# 2LD-17-mk-1_4_0.net
KiCad netlist of a schematic drawn in EAGLE
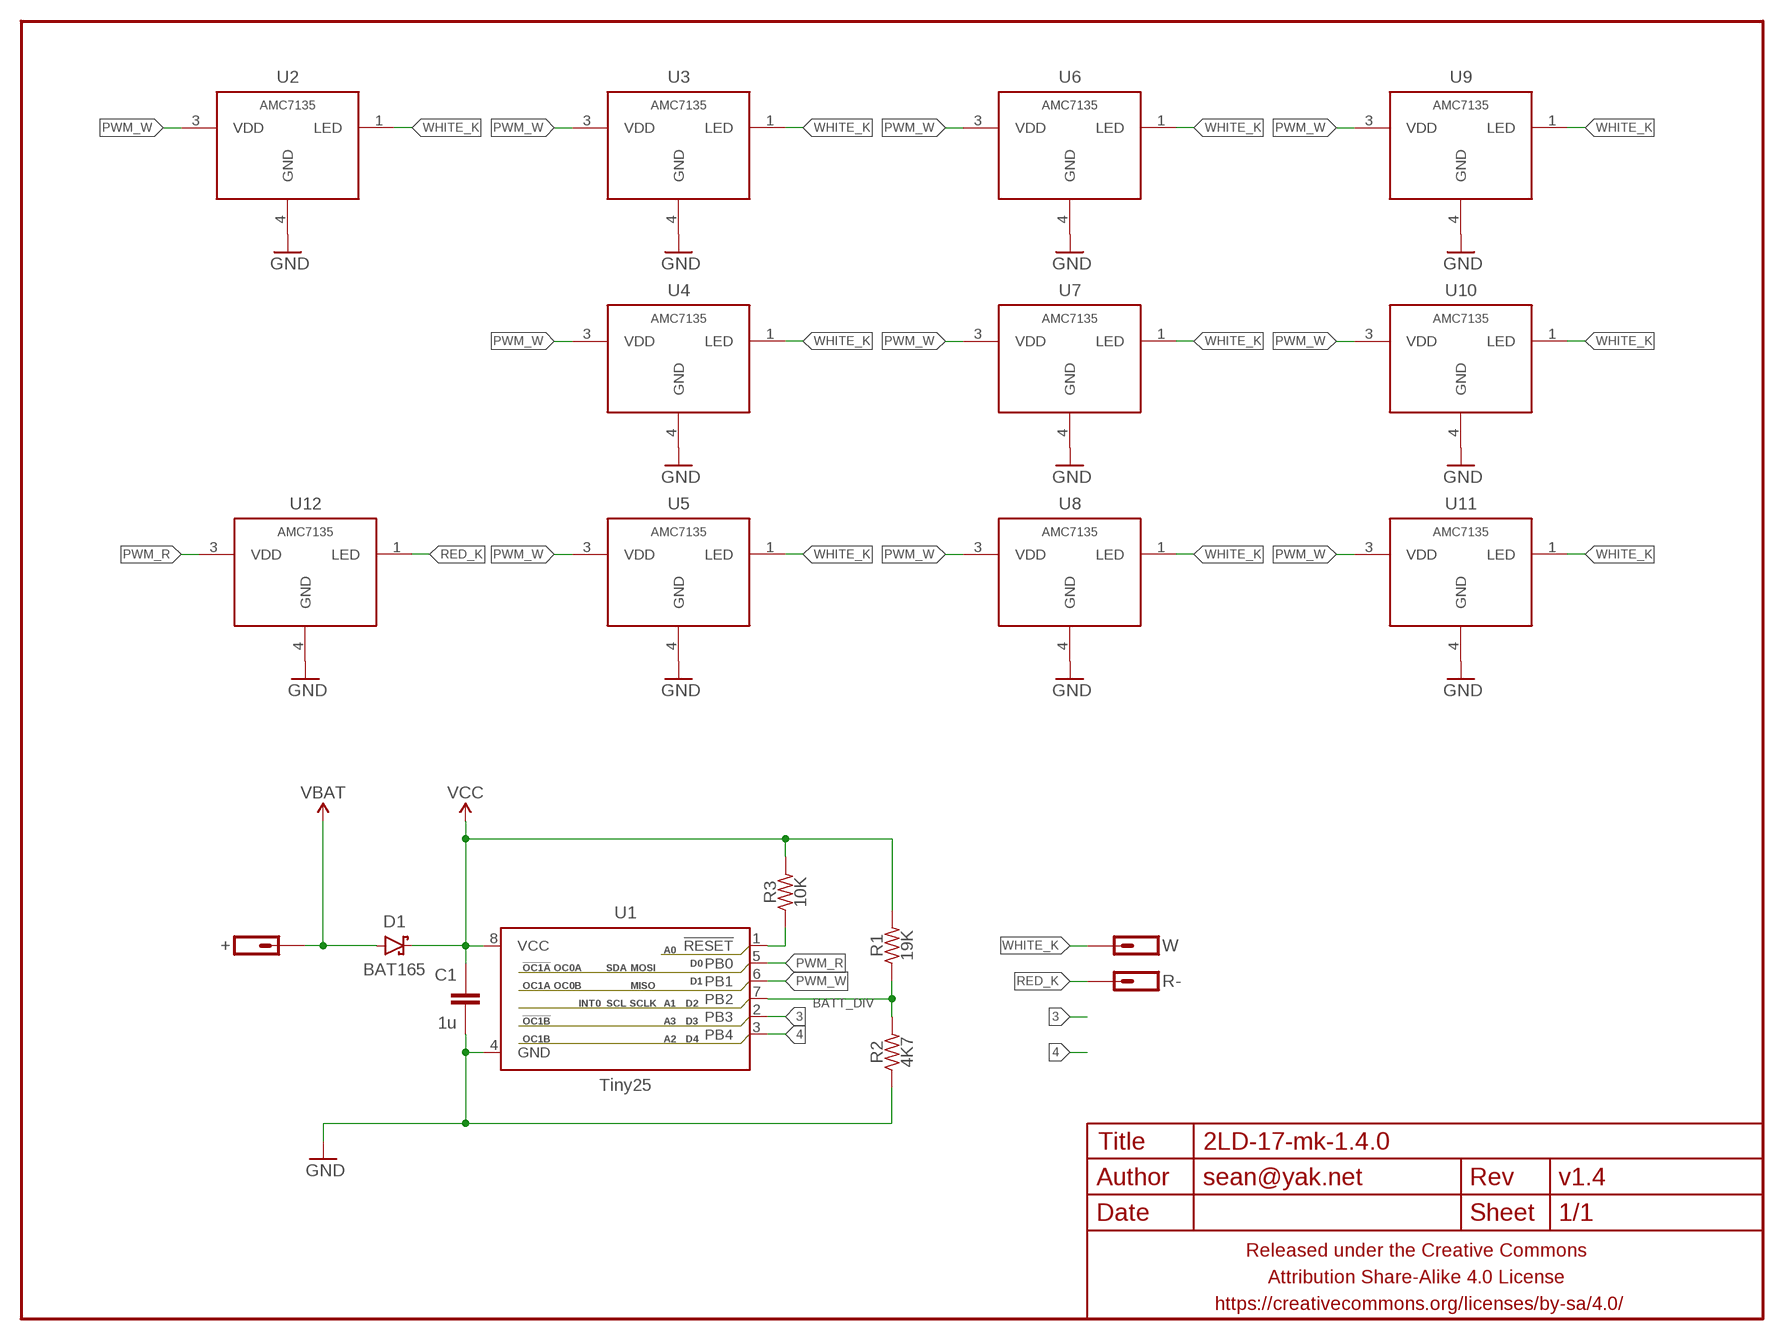
[diagram p0: schematic, sheet 1]

(export (version "E")
  (design (tool "Eeschema 10.0.6"))
  (components
    (comp (ref "+")
      (value "M011X01-0.9MM-CIR")
      (footprint "eagle-import:1X01-0.9MM-CIR")
      (libsource (lib "eagle-import") (part "M011X01-0.9MM-CIR"))
    )
    (comp (ref "C1")
      (value "1u")
      (footprint "eagle-import:C0402")
      (libsource (lib "eagle-import") (part "CAPACITOR-CERAMICC0402"))
    )
    (comp (ref "D1")
      (value "BAT165")
      (footprint "eagle-import:SOD323-SCHOTTKY")
      (libsource (lib "eagle-import") (part "DIODE-SCHOTTKYSOD323"))
    )
    (comp (ref "FRAME1")
      (value "FRAME-LETTERNO_PACKAGE")
      (footprint "eagle-import:DUMMY")
      (fields (field (name "DESIGNER") "sean@yak.net") (field (name "VERSION") "v1.4"))
      (libsource (lib "eagle-import") (part "FRAME-LETTERNO_PACKAGE"))
    )
    (comp (ref "R-")
      (value "M01SMD-1MM-DIA-NS")
      (footprint "eagle-import:1X01-SMD-1MM-DIA-NS")
      (libsource (lib "eagle-import") (part "M01SMD-1MM-DIA-NS"))
    )
    (comp (ref "R1")
      (value "19K")
      (footprint "eagle-import:R0402")
      (libsource (lib "eagle-import") (part "RESISTORR0402"))
    )
    (comp (ref "R2")
      (value "4K7")
      (footprint "eagle-import:R0402")
      (libsource (lib "eagle-import") (part "RESISTORR0402"))
    )
    (comp (ref "R3")
      (value "10K")
      (footprint "eagle-import:R0402")
      (libsource (lib "eagle-import") (part "RESISTORR0402"))
    )
    (comp (ref "U1")
      (value "Tiny25")
      (footprint "eagle-import:SO08-NARROWER")
      (libsource (lib "eagle-import") (part "ATTINY13SOIC-NARROWPADS"))
    )
    (comp (ref "U2")
      (value "AMC7135")
      (footprint "eagle-import:SOT89-NOTHERM-ROUNDED-LESS")
      (libsource (lib "eagle-import") (part "AMC7135SOT-89-NOTHERM-ROUNDED-LESS"))
    )
    (comp (ref "U3")
      (value "AMC7135")
      (footprint "eagle-import:SOT89-NOTHERM-ROUNDED-LESS")
      (libsource (lib "eagle-import") (part "AMC7135SOT-89-NOTHERM-ROUNDED-LESS"))
    )
    (comp (ref "U4")
      (value "AMC7135")
      (footprint "eagle-import:SOT89-NOTHERM-ROUNDED-LESS")
      (libsource (lib "eagle-import") (part "AMC7135SOT-89-NOTHERM-ROUNDED-LESS"))
    )
    (comp (ref "U5")
      (value "AMC7135")
      (footprint "eagle-import:SOT89-NOTHERM-ROUNDED-LESS")
      (libsource (lib "eagle-import") (part "AMC7135SOT-89-NOTHERM-ROUNDED-LESS"))
    )
    (comp (ref "U6")
      (value "AMC7135")
      (footprint "eagle-import:SOT89-NOTHERM-ROUNDED-LESS")
      (libsource (lib "eagle-import") (part "AMC7135SOT-89-NOTHERM-ROUNDED-LESS"))
    )
    (comp (ref "U7")
      (value "AMC7135")
      (footprint "eagle-import:SOT89-NOTHERM-ROUNDED-LESS")
      (libsource (lib "eagle-import") (part "AMC7135SOT-89-NOTHERM-ROUNDED-LESS"))
    )
    (comp (ref "U8")
      (value "AMC7135")
      (footprint "eagle-import:SOT89-NOTHERM-ROUNDED-LESS")
      (libsource (lib "eagle-import") (part "AMC7135SOT-89-NOTHERM-ROUNDED-LESS"))
    )
    (comp (ref "U9")
      (value "AMC7135")
      (footprint "eagle-import:SOT89-NOTHERM-ROUNDED-LESS")
      (libsource (lib "eagle-import") (part "AMC7135SOT-89-NOTHERM-ROUNDED-LESS"))
    )
    (comp (ref "U10")
      (value "AMC7135")
      (footprint "eagle-import:SOT89-NOTHERM-ROUNDED-LESS")
      (libsource (lib "eagle-import") (part "AMC7135SOT-89-NOTHERM-ROUNDED-LESS"))
    )
    (comp (ref "U11")
      (value "AMC7135")
      (footprint "eagle-import:SOT89-NOTHERM-ROUNDED-LESS")
      (libsource (lib "eagle-import") (part "AMC7135SOT-89-NOTHERM-ROUNDED-LESS"))
    )
    (comp (ref "U12")
      (value "AMC7135")
      (footprint "eagle-import:SOT89-NOTHERM-ROUNDED-LESS")
      (libsource (lib "eagle-import") (part "AMC7135SOT-89-NOTHERM-ROUNDED-LESS"))
    )
    (comp (ref "W")
      (value "M011X01-0.9MM-CIR")
      (footprint "eagle-import:1X01-0.9MM-CIR")
      (libsource (lib "eagle-import") (part "M011X01-0.9MM-CIR"))
    )
  )
  (nets
    (net (code "1") (name "/BATT_DIV") (class "Default")
      (node (ref "R1") (pin "1") (pinfunction "1_1") (pintype "passive"))
      (node (ref "R2") (pin "2") (pinfunction "2_2") (pintype "passive"))
      (node (ref "U1") (pin "7") (pinfunction "PB2_7") (pintype "bidirectional"))
    )
    (net (code "2") (name "3") (class "Default")
      (node (ref "U1") (pin "2") (pinfunction "PB3_2") (pintype "bidirectional"))
    )
    (net (code "3") (name "4") (class "Default")
      (node (ref "U1") (pin "3") (pinfunction "PB4_3") (pintype "bidirectional"))
    )
    (net (code "4") (name "GND") (class "Default")
      (node (ref "C1") (pin "2") (pinfunction "2_2") (pintype "passive"))
      (node (ref "R2") (pin "1") (pinfunction "1_1") (pintype "passive"))
      (node (ref "U1") (pin "4") (pinfunction "GND_4") (pintype "bidirectional"))
      (node (ref "U10") (pin "4") (pinfunction "GND_4") (pintype "bidirectional"))
      (node (ref "U11") (pin "4") (pinfunction "GND_4") (pintype "bidirectional"))
      (node (ref "U12") (pin "4") (pinfunction "GND_4") (pintype "bidirectional"))
      (node (ref "U2") (pin "4") (pinfunction "GND_4") (pintype "bidirectional"))
      (node (ref "U3") (pin "4") (pinfunction "GND_4") (pintype "bidirectional"))
      (node (ref "U4") (pin "4") (pinfunction "GND_4") (pintype "bidirectional"))
      (node (ref "U5") (pin "4") (pinfunction "GND_4") (pintype "bidirectional"))
      (node (ref "U6") (pin "4") (pinfunction "GND_4") (pintype "bidirectional"))
      (node (ref "U7") (pin "4") (pinfunction "GND_4") (pintype "bidirectional"))
      (node (ref "U8") (pin "4") (pinfunction "GND_4") (pintype "bidirectional"))
      (node (ref "U9") (pin "4") (pinfunction "GND_4") (pintype "bidirectional"))
    )
    (net (code "5") (name "Net-(U1-~{RESET})") (class "Default")
      (node (ref "R3") (pin "1") (pinfunction "1_1") (pintype "passive"))
      (node (ref "U1") (pin "1") (pinfunction "~{RESET}_1") (pintype "bidirectional"))
    )
    (net (code "6") (name "PWM_R") (class "Default")
      (node (ref "U1") (pin "5") (pinfunction "PB0_5") (pintype "bidirectional"))
      (node (ref "U12") (pin "3") (pinfunction "VDD_3") (pintype "bidirectional"))
    )
    (net (code "7") (name "PWM_W") (class "Default")
      (node (ref "U1") (pin "6") (pinfunction "PB1_6") (pintype "bidirectional"))
      (node (ref "U10") (pin "3") (pinfunction "VDD_3") (pintype "bidirectional"))
      (node (ref "U11") (pin "3") (pinfunction "VDD_3") (pintype "bidirectional"))
      (node (ref "U2") (pin "3") (pinfunction "VDD_3") (pintype "bidirectional"))
      (node (ref "U3") (pin "3") (pinfunction "VDD_3") (pintype "bidirectional"))
      (node (ref "U4") (pin "3") (pinfunction "VDD_3") (pintype "bidirectional"))
      (node (ref "U5") (pin "3") (pinfunction "VDD_3") (pintype "bidirectional"))
      (node (ref "U6") (pin "3") (pinfunction "VDD_3") (pintype "bidirectional"))
      (node (ref "U7") (pin "3") (pinfunction "VDD_3") (pintype "bidirectional"))
      (node (ref "U8") (pin "3") (pinfunction "VDD_3") (pintype "bidirectional"))
      (node (ref "U9") (pin "3") (pinfunction "VDD_3") (pintype "bidirectional"))
    )
    (net (code "8") (name "RED_K") (class "Default")
      (node (ref "R-") (pin "P$1") (pinfunction "1_P$1") (pintype "passive"))
      (node (ref "U12") (pin "1") (pinfunction "LED_1") (pintype "bidirectional"))
    )
    (net (code "9") (name "VBAT") (class "Default")
      (node (ref "+") (pin "P$1") (pinfunction "1_P$1") (pintype "passive"))
      (node (ref "D1") (pin "A") (pinfunction "A_A") (pintype "passive"))
    )
    (net (code "10") (name "VCC") (class "Default")
      (node (ref "C1") (pin "1") (pinfunction "1_1") (pintype "passive"))
      (node (ref "D1") (pin "C") (pinfunction "C_C") (pintype "passive"))
      (node (ref "R1") (pin "2") (pinfunction "2_2") (pintype "passive"))
      (node (ref "R3") (pin "2") (pinfunction "2_2") (pintype "passive"))
      (node (ref "U1") (pin "8") (pinfunction "VCC_8") (pintype "bidirectional"))
    )
    (net (code "11") (name "WHITE_K") (class "Default")
      (node (ref "U10") (pin "1") (pinfunction "LED_1") (pintype "bidirectional"))
      (node (ref "U11") (pin "1") (pinfunction "LED_1") (pintype "bidirectional"))
      (node (ref "U2") (pin "1") (pinfunction "LED_1") (pintype "bidirectional"))
      (node (ref "U3") (pin "1") (pinfunction "LED_1") (pintype "bidirectional"))
      (node (ref "U4") (pin "1") (pinfunction "LED_1") (pintype "bidirectional"))
      (node (ref "U5") (pin "1") (pinfunction "LED_1") (pintype "bidirectional"))
      (node (ref "U6") (pin "1") (pinfunction "LED_1") (pintype "bidirectional"))
      (node (ref "U7") (pin "1") (pinfunction "LED_1") (pintype "bidirectional"))
      (node (ref "U8") (pin "1") (pinfunction "LED_1") (pintype "bidirectional"))
      (node (ref "U9") (pin "1") (pinfunction "LED_1") (pintype "bidirectional"))
      (node (ref "W") (pin "P$1") (pinfunction "1_P$1") (pintype "passive"))
    )
  )
)
